# rgb-matrix-backpack-5a.net
KiCad netlist of a schematic drawn in EAGLE
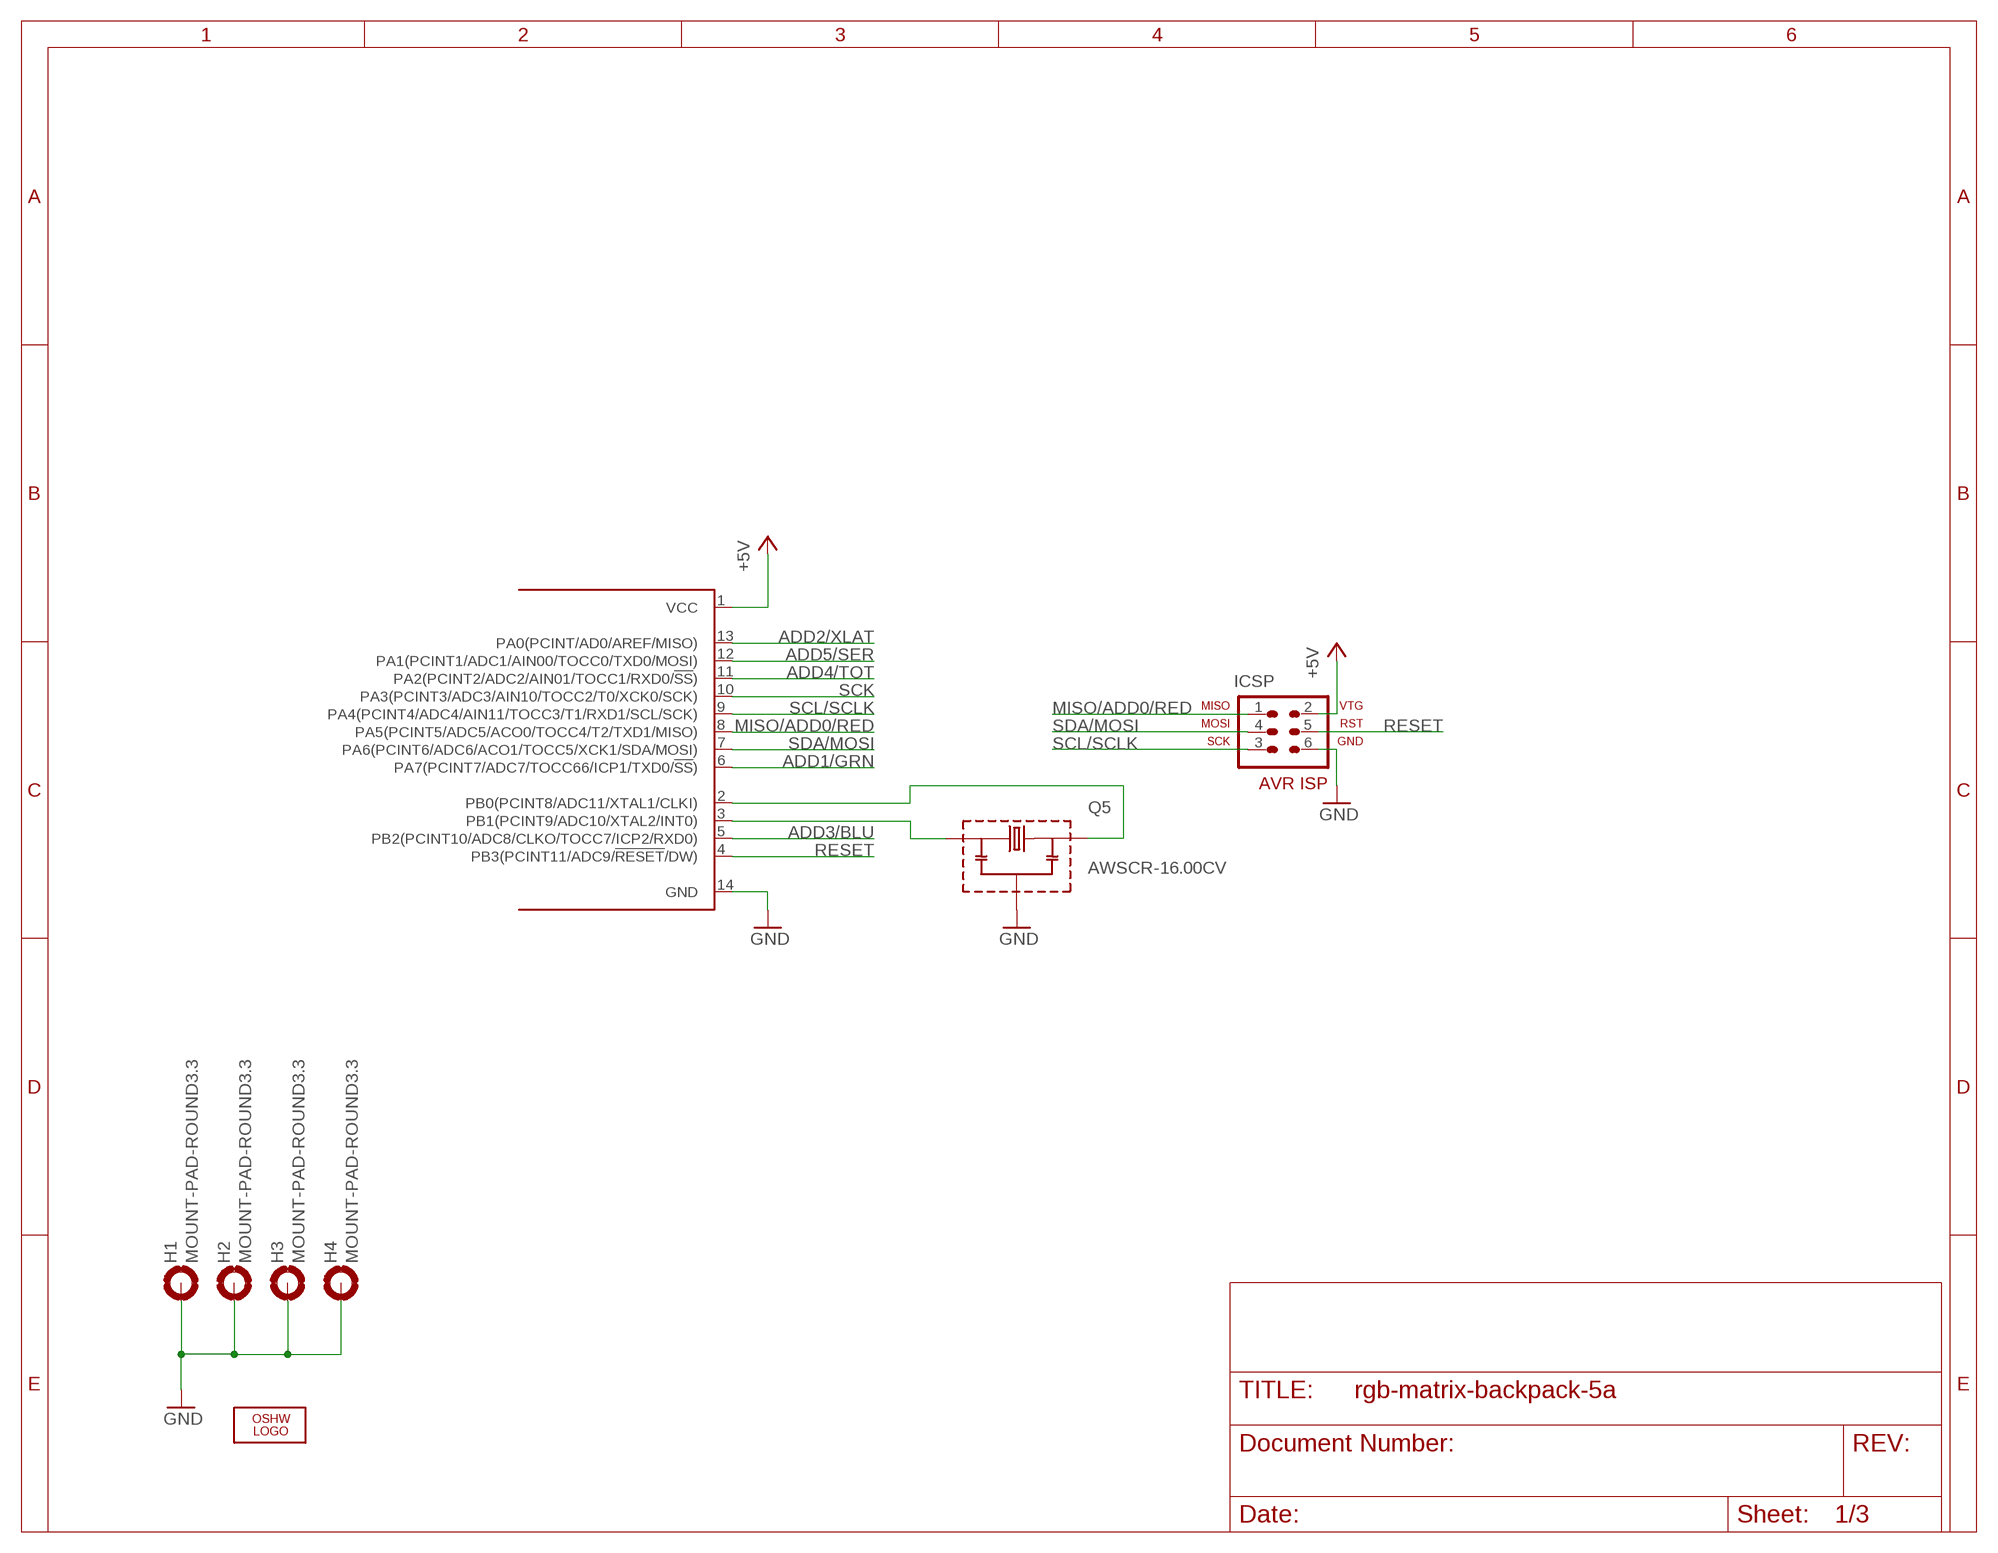
[diagram p0: schematic, sheet 1]
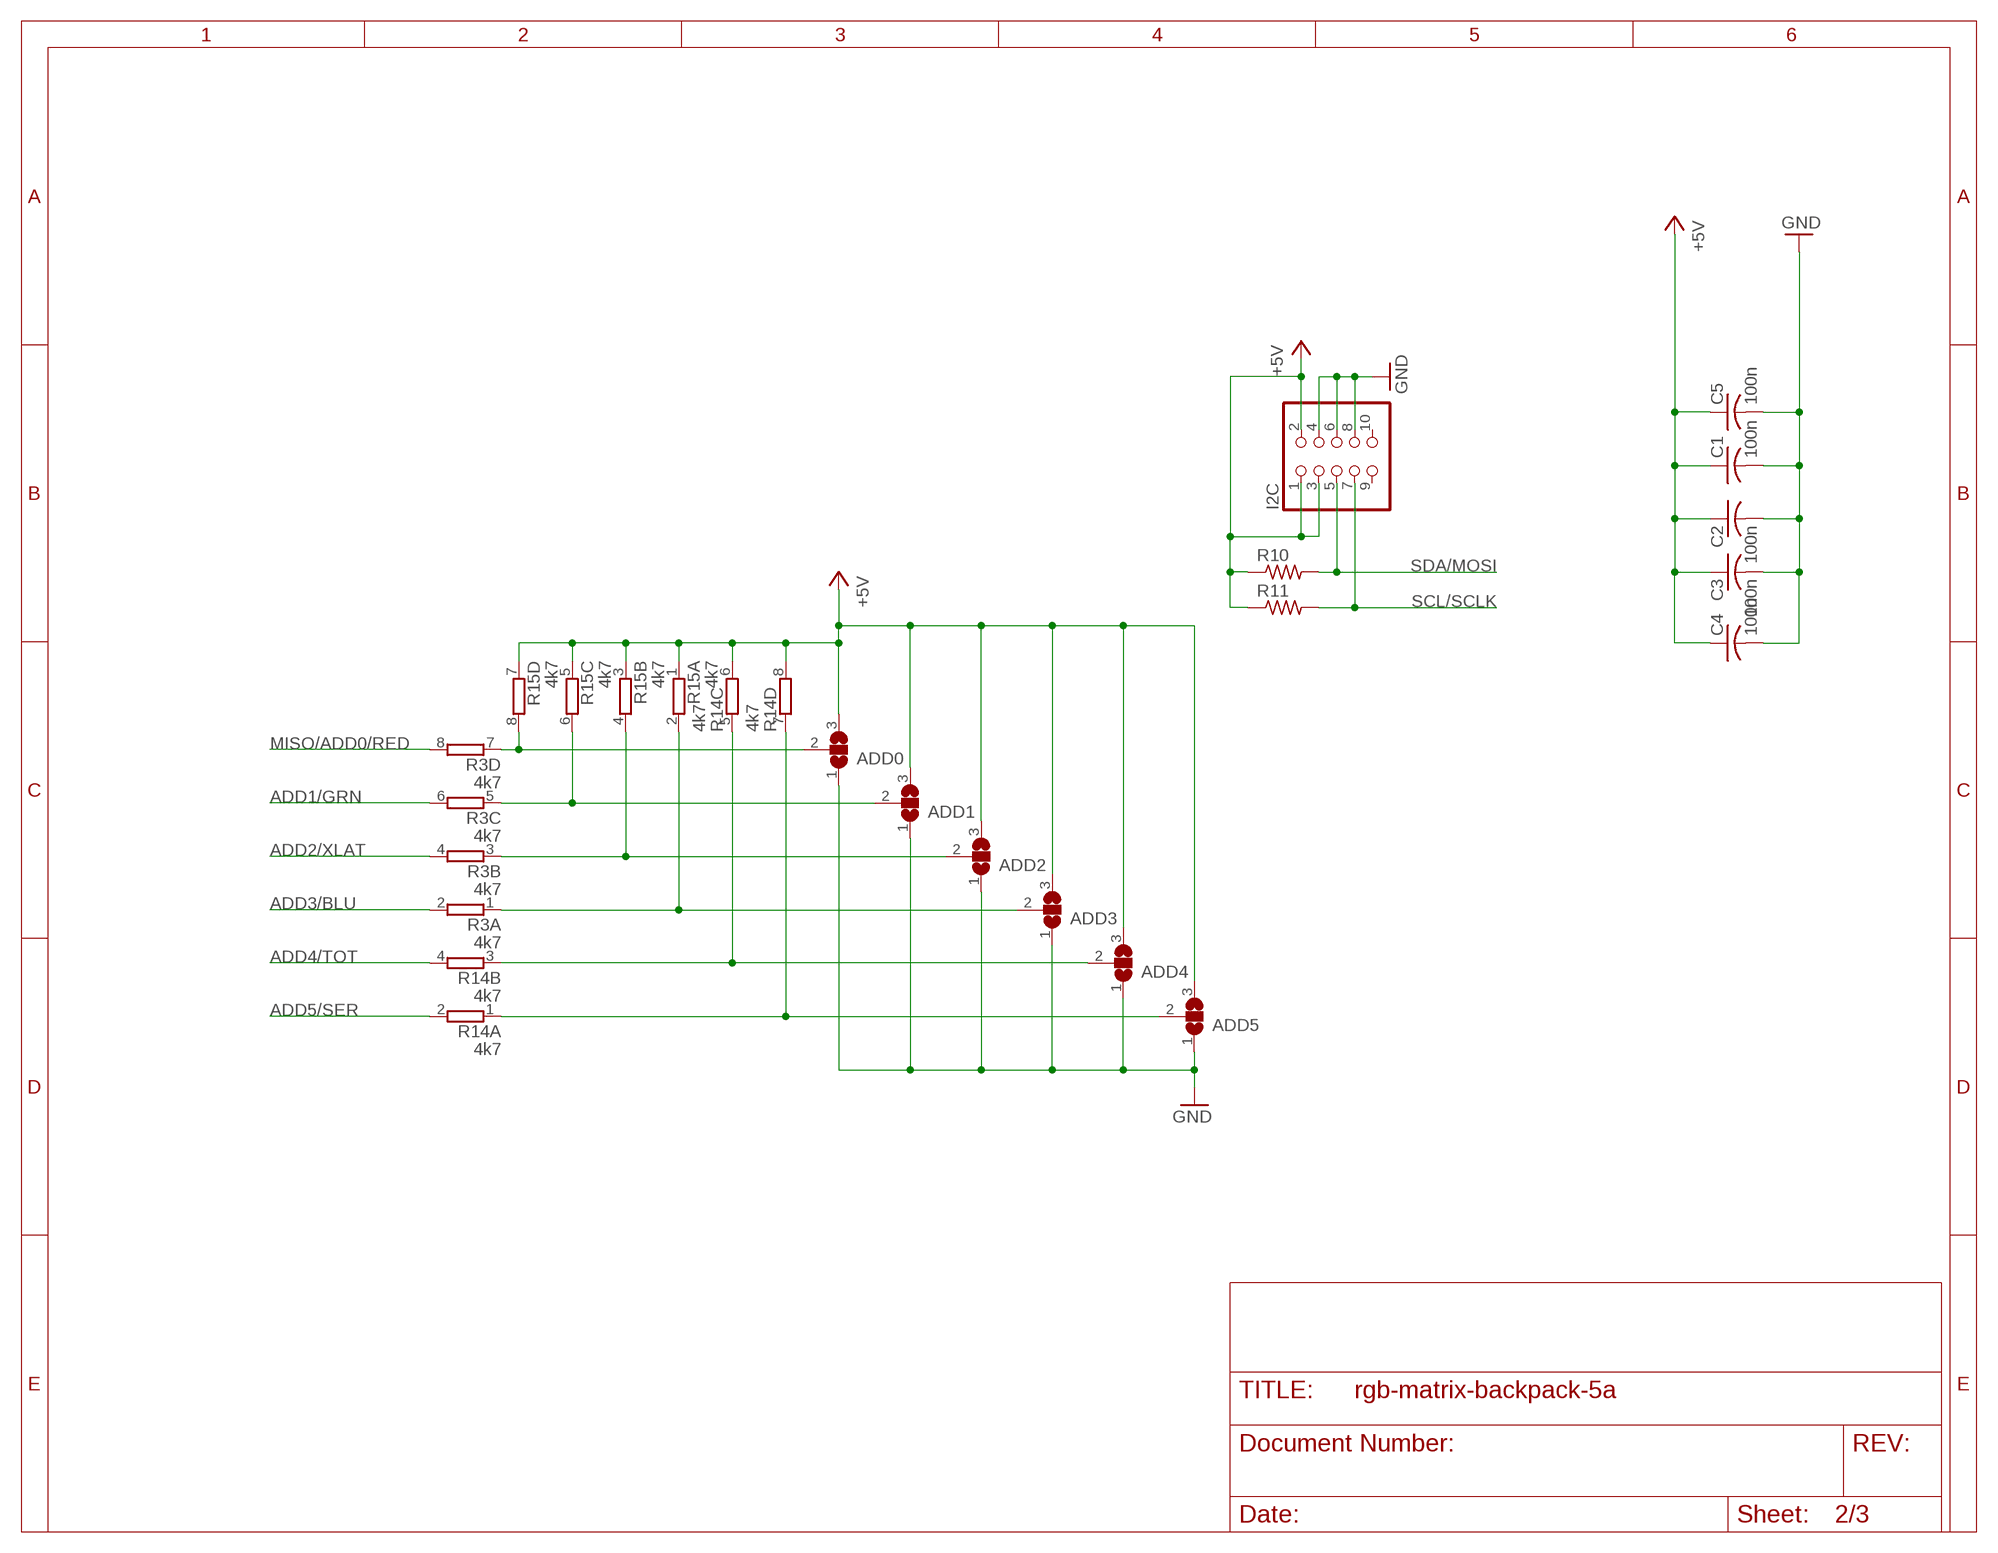
[diagram p1: schematic, sheet 2]
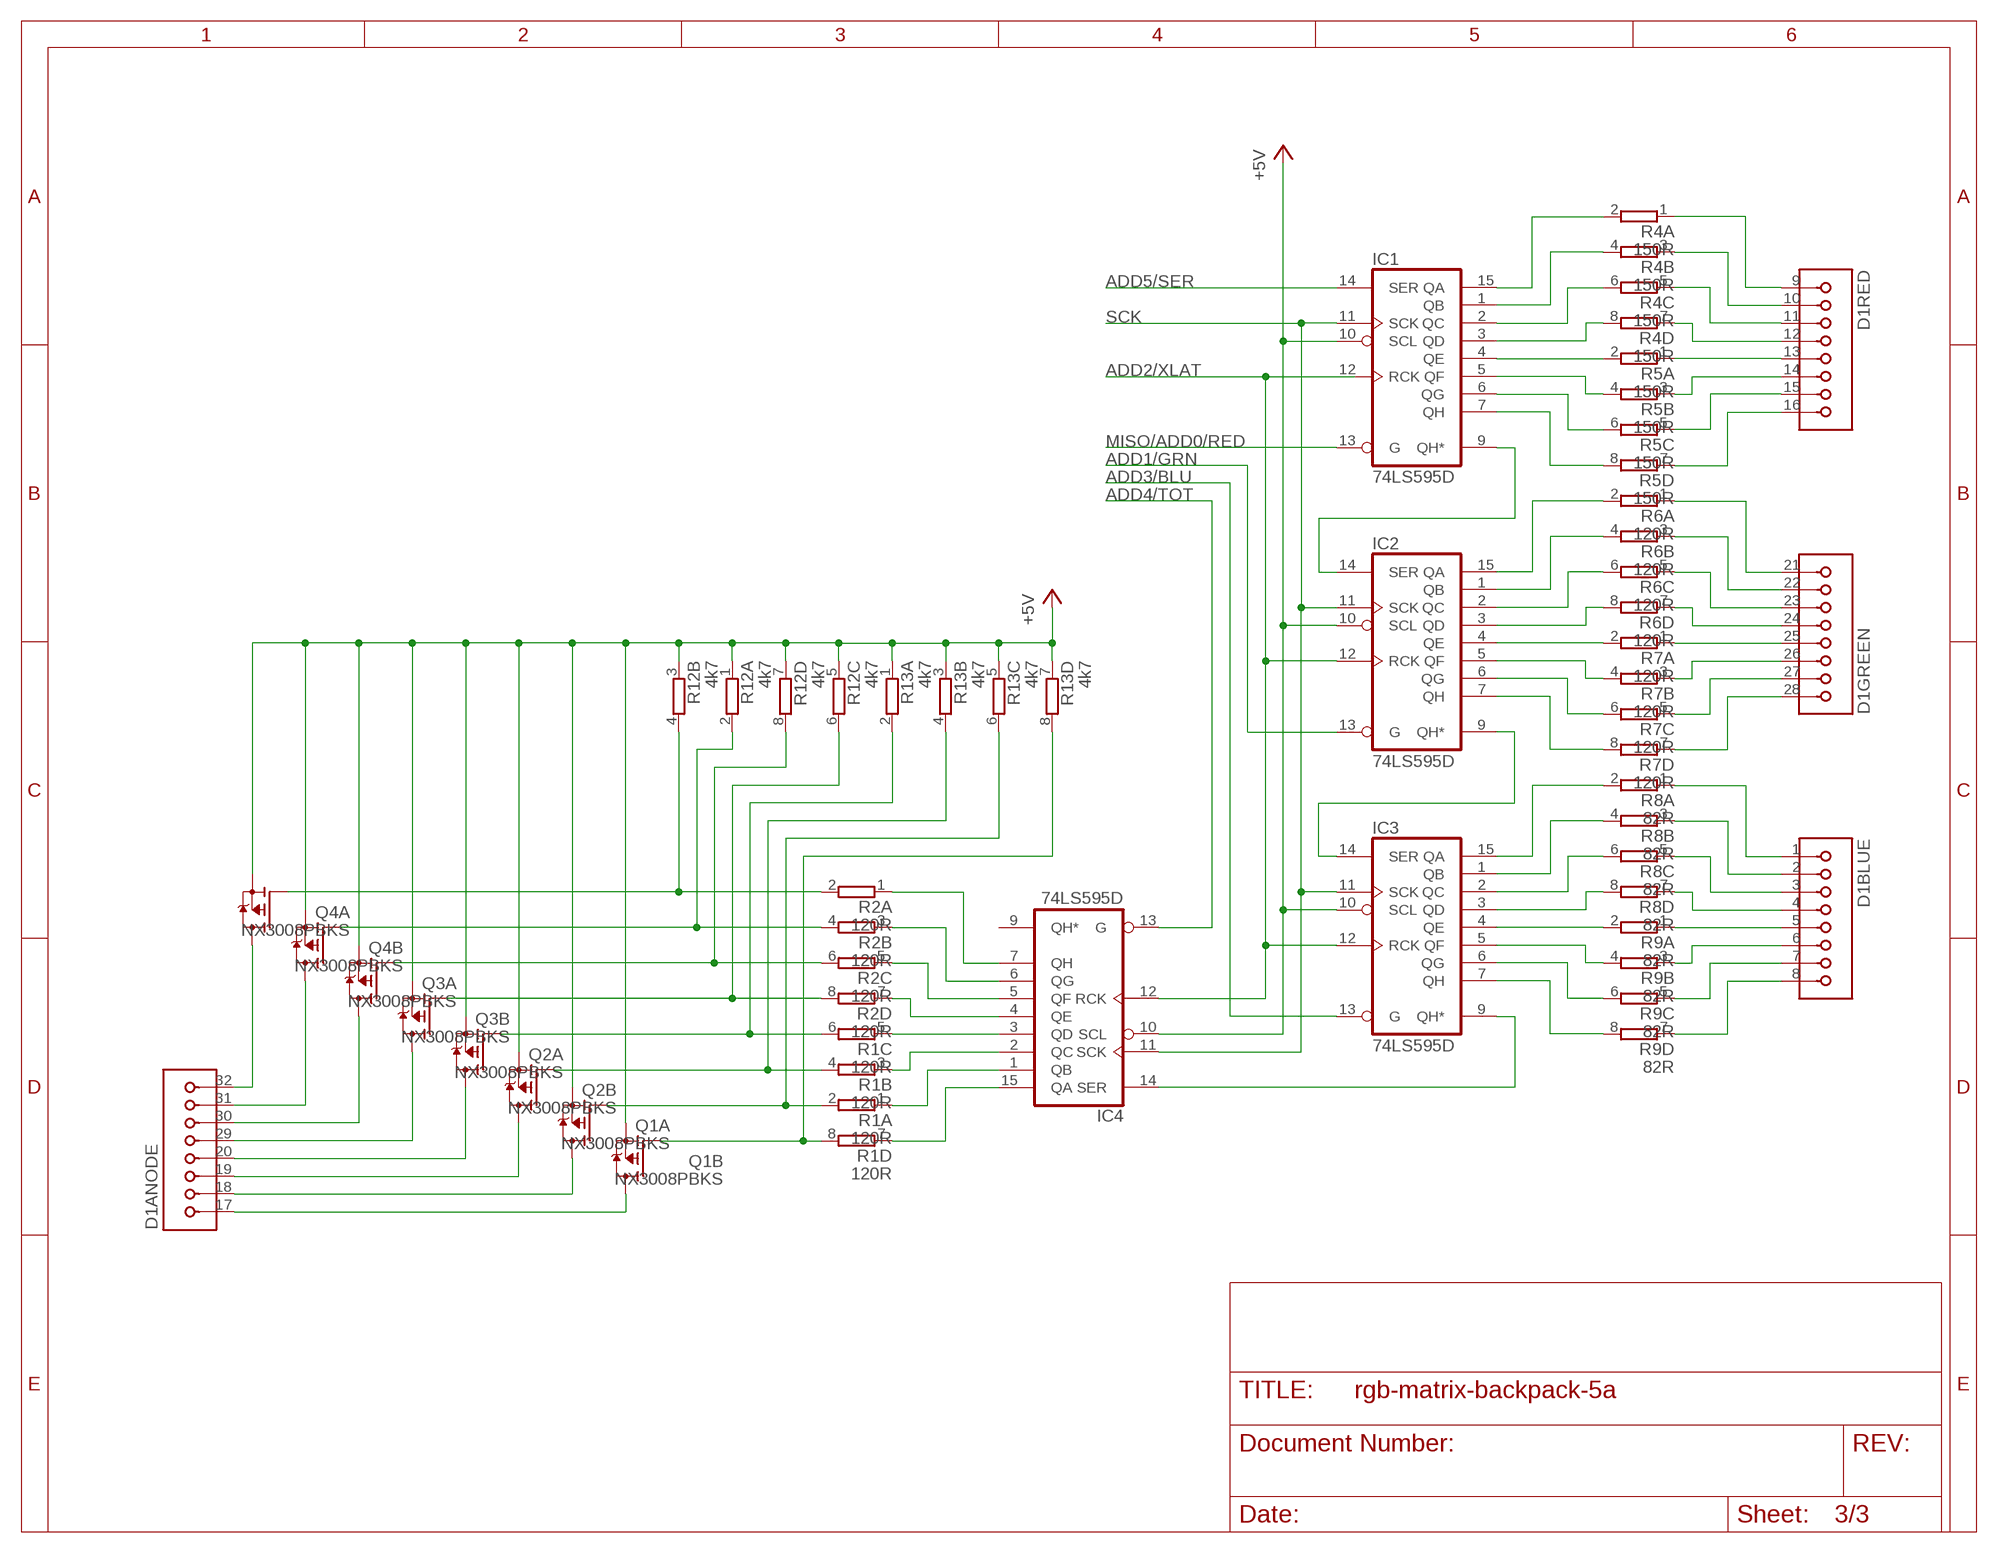
[diagram p2: schematic, sheet 3]

(export (version "E")
  (design (tool "Eeschema 10.0.6"))
  (components
    (comp (ref "ADD0")
      (value "SJ2W")
      (footprint "eagle-import:SJ_2")
      (libsource (lib "eagle-import") (part "SJ2W"))
    )
    (comp (ref "ADD1")
      (value "SJ2W")
      (footprint "eagle-import:SJ_2")
      (libsource (lib "eagle-import") (part "SJ2W"))
    )
    (comp (ref "ADD2")
      (value "SJ2W")
      (footprint "eagle-import:SJ_2")
      (libsource (lib "eagle-import") (part "SJ2W"))
    )
    (comp (ref "ADD3")
      (value "SJ2W")
      (footprint "eagle-import:SJ_2")
      (libsource (lib "eagle-import") (part "SJ2W"))
    )
    (comp (ref "ADD4")
      (value "SJ2W")
      (footprint "eagle-import:SJ_2")
      (libsource (lib "eagle-import") (part "SJ2W"))
    )
    (comp (ref "ADD5")
      (value "SJ2W")
      (footprint "eagle-import:SJ_2")
      (libsource (lib "eagle-import") (part "SJ2W"))
    )
    (comp (ref "C1")
      (value "100n")
      (footprint "eagle-import:C0603")
      (fields (field (name "PARTNO") "CC0603MRY5V9BB104"))
      (libsource (lib "eagle-import") (part "C-USC0603"))
    )
    (comp (ref "C2")
      (value "100n")
      (footprint "eagle-import:C0603")
      (fields (field (name "PARTNO") "CC0603MRY5V9BB104"))
      (libsource (lib "eagle-import") (part "C-USC0603"))
    )
    (comp (ref "C3")
      (value "100n")
      (footprint "eagle-import:C0603")
      (fields (field (name "PARTNO") "CC0603ZRY5V7BB105"))
      (libsource (lib "eagle-import") (part "C-USC0603"))
    )
    (comp (ref "C4")
      (value "100n")
      (footprint "eagle-import:C0603")
      (fields (field (name "PARTNO") "CC0603MRY5V9BB104"))
      (libsource (lib "eagle-import") (part "C-USC0603"))
    )
    (comp (ref "C5")
      (value "100n")
      (footprint "eagle-import:C0603")
      (fields (field (name "PARTNO") "CC0603MRY5V9BB104"))
      (libsource (lib "eagle-import") (part "C-USC0603"))
    )
    (comp (ref "I2C")
      (value "PINHD-2X5_2.54-90°")
      (footprint "eagle-import:2X05_90")
      (libsource (lib "eagle-import") (part "PINHD-2X5_2.54-90°"))
    )
    (comp (ref "R3")
      (value "4k7")
      (footprint "eagle-import:CTS742C083-RES")
      (fields (field (name "PARTNO") "742C083102JPTR"))
      (libsource (lib "eagle-import") (part "4R-NCTS742C083"))
    )
    (comp (ref "R10")
      (value "R-US_0207/2V")
      (footprint "eagle-import:0207_2V")
      (fields (field (name "PARTNO") "CF14JT4K70"))
      (libsource (lib "eagle-import") (part "R-US_0207/2V"))
    )
    (comp (ref "R11")
      (value "R-US_0207/2V")
      (footprint "eagle-import:0207_2V")
      (fields (field (name "PARTNO") "CF14JT4K70"))
      (libsource (lib "eagle-import") (part "R-US_0207/2V"))
    )
    (comp (ref "R14")
      (value "4k7")
      (footprint "eagle-import:CTS742C083-RES")
      (fields (field (name "PARTNO") "742C083102JPTR"))
      (libsource (lib "eagle-import") (part "4R-NCTS742C083"))
    )
    (comp (ref "R15")
      (value "4k7")
      (footprint "eagle-import:CTS742C083-RES")
      (fields (field (name "PARTNO") "742C083102JPTR"))
      (libsource (lib "eagle-import") (part "4R-NCTS742C083"))
    )
    (comp (ref "D1")
      (value "60MM-8X8-RGB-LED-ARRAY")
      (footprint "eagle-import:60MM-8X8-RGB-MATRIX")
      (fields (field (name "BOM") "EXCLUDE") (field (name "DNP") "T"))
      (libsource (lib "eagle-import") (part "60MM-8X8-RGB-LED-ARRAY"))
    )
    (comp (ref "IC1")
      (value "74LS595D")
      (footprint "eagle-import:SO16")
      (libsource (lib "eagle-import") (part "74595DLS"))
    )
    (comp (ref "IC2")
      (value "74LS595D")
      (footprint "eagle-import:SO16")
      (libsource (lib "eagle-import") (part "74595DLS"))
    )
    (comp (ref "IC3")
      (value "74LS595D")
      (footprint "eagle-import:SO16")
      (libsource (lib "eagle-import") (part "74595DLS"))
    )
    (comp (ref "IC4")
      (value "74LS595D")
      (footprint "eagle-import:SO16")
      (libsource (lib "eagle-import") (part "74595DLS"))
    )
    (comp (ref "Q1")
      (value "NX3008PBKS")
      (footprint "eagle-import:SOT363_INFINEON")
      (fields (field (name "PARTNO") "NX3008PBKS"))
      (libsource (lib "eagle-import") (part "BSD223P"))
    )
    (comp (ref "Q2")
      (value "NX3008PBKS")
      (footprint "eagle-import:SOT363_INFINEON")
      (libsource (lib "eagle-import") (part "BSD223P"))
    )
    (comp (ref "Q3")
      (value "NX3008PBKS")
      (footprint "eagle-import:SOT363_INFINEON")
      (libsource (lib "eagle-import") (part "BSD223P"))
    )
    (comp (ref "Q4")
      (value "NX3008PBKS")
      (footprint "eagle-import:SOT363_INFINEON")
      (libsource (lib "eagle-import") (part "BSD223P"))
    )
    (comp (ref "R1")
      (value "120R")
      (footprint "eagle-import:CTS742C083-RES")
      (fields (field (name "PARTNO") "742C083102JPTR"))
      (libsource (lib "eagle-import") (part "4R-NCTS742C083"))
    )
    (comp (ref "R2")
      (value "120R")
      (footprint "eagle-import:CTS742C083-RES")
      (fields (field (name "PARTNO") "742C083102JPTR"))
      (libsource (lib "eagle-import") (part "4R-NCTS742C083"))
    )
    (comp (ref "R4")
      (value "150R")
      (footprint "eagle-import:CTS742C083-RES")
      (fields (field (name "PARTNO") "742C083102JPTR"))
      (libsource (lib "eagle-import") (part "4R-NCTS742C083"))
    )
    (comp (ref "R5")
      (value "150R")
      (footprint "eagle-import:CTS742C083-RES")
      (fields (field (name "PARTNO") "742C083102JPTR"))
      (libsource (lib "eagle-import") (part "4R-NCTS742C083"))
    )
    (comp (ref "R6")
      (value "120R")
      (footprint "eagle-import:CTS742C083-RES")
      (fields (field (name "PARTNO") "742C083102JPTR"))
      (libsource (lib "eagle-import") (part "4R-NCTS742C083"))
    )
    (comp (ref "R7")
      (value "120R")
      (footprint "eagle-import:CTS742C083-RES")
      (fields (field (name "PARTNO") "742C083102JPTR"))
      (libsource (lib "eagle-import") (part "4R-NCTS742C083"))
    )
    (comp (ref "R8")
      (value "82R")
      (footprint "eagle-import:CTS742C083-RES")
      (fields (field (name "PARTNO") "742C083102JPTR"))
      (libsource (lib "eagle-import") (part "4R-NCTS742C083"))
    )
    (comp (ref "R9")
      (value "82R")
      (footprint "eagle-import:CTS742C083-RES")
      (fields (field (name "PARTNO") "742C083102JPTR"))
      (libsource (lib "eagle-import") (part "4R-NCTS742C083"))
    )
    (comp (ref "R12")
      (value "4k7")
      (footprint "eagle-import:CTS742C083-RES")
      (fields (field (name "PARTNO") "742C083102JPTR"))
      (libsource (lib "eagle-import") (part "4R-NCTS742C083"))
    )
    (comp (ref "R13")
      (value "4k7")
      (footprint "eagle-import:CTS742C083-RES")
      (fields (field (name "PARTNO") "742C083102JPTR"))
      (libsource (lib "eagle-import") (part "4R-NCTS742C083"))
    )
    (comp (ref "H1")
      (value "MOUNT-PAD-ROUND3.3")
      (footprint "eagle-import:3,3-PAD")
      (libsource (lib "eagle-import") (part "MOUNT-PAD-ROUND3.3"))
    )
    (comp (ref "H2")
      (value "MOUNT-PAD-ROUND3.3")
      (footprint "eagle-import:3,3-PAD")
      (libsource (lib "eagle-import") (part "MOUNT-PAD-ROUND3.3"))
    )
    (comp (ref "H3")
      (value "MOUNT-PAD-ROUND3.3")
      (footprint "eagle-import:3,3-PAD")
      (libsource (lib "eagle-import") (part "MOUNT-PAD-ROUND3.3"))
    )
    (comp (ref "H4")
      (value "MOUNT-PAD-ROUND3.3")
      (footprint "eagle-import:3,3-PAD")
      (libsource (lib "eagle-import") (part "MOUNT-PAD-ROUND3.3"))
    )
    (comp (ref "ICSP")
      (value "AVR-ISP-6")
      (footprint "eagle-import:AVR-ISP-6")
      (libsource (lib "eagle-import") (part "AVR-ISP-6"))
    )
    (comp (ref "LOGO1")
      (value "OSHW_LOGO_FILLX0350-NT")
      (footprint "eagle-import:OSHW_FILLX350_NOTEXT")
      (libsource (lib "eagle-import") (part "OSHW_LOGO_FILLX0350-NT"))
    )
    (comp (ref "Q5")
      (value "AWSCR-16.00CV")
      (footprint "eagle-import:AWSCR")
      (libsource (lib "eagle-import") (part "AWSCR-16.00CV"))
    )
    (comp (ref "U1")
      (value "ATTINY841-SU")
      (footprint "eagle-import:SO14")
      (libsource (lib "eagle-import") (part "ATTINY841-SU"))
    )
  )
  (nets
    (net (code "1") (name "+5V") (class "Default")
      (node (ref "ADD0") (pin "3") (pinfunction "3_3") (pintype "passive"))
      (node (ref "ADD1") (pin "3") (pinfunction "3_3") (pintype "passive"))
      (node (ref "ADD2") (pin "3") (pinfunction "3_3") (pintype "passive"))
      (node (ref "ADD3") (pin "3") (pinfunction "3_3") (pintype "passive"))
      (node (ref "ADD4") (pin "3") (pinfunction "3_3") (pintype "passive"))
      (node (ref "ADD5") (pin "3") (pinfunction "3_3") (pintype "passive"))
      (node (ref "C1") (pin "1") (pinfunction "1_1") (pintype "passive"))
      (node (ref "C2") (pin "1") (pinfunction "1_1") (pintype "passive"))
      (node (ref "C3") (pin "1") (pinfunction "1_1") (pintype "passive"))
      (node (ref "C4") (pin "1") (pinfunction "1_1") (pintype "passive"))
      (node (ref "C5") (pin "1") (pinfunction "1_1") (pintype "passive"))
      (node (ref "I2C") (pin "1") (pinfunction "1_1") (pintype "passive"))
      (node (ref "I2C") (pin "2") (pinfunction "2_2") (pintype "passive"))
      (node (ref "I2C") (pin "3") (pinfunction "3_3") (pintype "passive"))
      (node (ref "IC1") (pin "10") (pinfunction "SCL_10") (pintype "input"))
      (node (ref "IC2") (pin "10") (pinfunction "SCL_10") (pintype "input"))
      (node (ref "IC3") (pin "10") (pinfunction "SCL_10") (pintype "input"))
      (node (ref "IC4") (pin "10") (pinfunction "SCL_10") (pintype "input"))
      (node (ref "ICSP") (pin "2") (pinfunction "2_2") (pintype "passive"))
      (node (ref "Q1") (pin "1") (pinfunction "S_1") (pintype "passive"))
      (node (ref "Q1") (pin "4") (pinfunction "S_4") (pintype "passive"))
      (node (ref "Q2") (pin "1") (pinfunction "S_1") (pintype "passive"))
      (node (ref "Q2") (pin "4") (pinfunction "S_4") (pintype "passive"))
      (node (ref "Q3") (pin "1") (pinfunction "S_1") (pintype "passive"))
      (node (ref "Q3") (pin "4") (pinfunction "S_4") (pintype "passive"))
      (node (ref "Q4") (pin "1") (pinfunction "S_1") (pintype "passive"))
      (node (ref "Q4") (pin "4") (pinfunction "S_4") (pintype "passive"))
      (node (ref "R10") (pin "1") (pinfunction "1_1") (pintype "passive"))
      (node (ref "R11") (pin "1") (pinfunction "1_1") (pintype "passive"))
      (node (ref "R12") (pin "1") (pinfunction "1_1") (pintype "passive"))
      (node (ref "R12") (pin "3") (pinfunction "1_3") (pintype "passive"))
      (node (ref "R12") (pin "5") (pinfunction "1_5") (pintype "passive"))
      (node (ref "R12") (pin "7") (pinfunction "1_7") (pintype "passive"))
      (node (ref "R13") (pin "1") (pinfunction "1_1") (pintype "passive"))
      (node (ref "R13") (pin "3") (pinfunction "1_3") (pintype "passive"))
      (node (ref "R13") (pin "5") (pinfunction "1_5") (pintype "passive"))
      (node (ref "R13") (pin "7") (pinfunction "1_7") (pintype "passive"))
      (node (ref "R14") (pin "6") (pinfunction "2_6") (pintype "passive"))
      (node (ref "R14") (pin "8") (pinfunction "2_8") (pintype "passive"))
      (node (ref "R15") (pin "1") (pinfunction "1_1") (pintype "passive"))
      (node (ref "R15") (pin "3") (pinfunction "1_3") (pintype "passive"))
      (node (ref "R15") (pin "5") (pinfunction "1_5") (pintype "passive"))
      (node (ref "R15") (pin "7") (pinfunction "1_7") (pintype "passive"))
      (node (ref "U1") (pin "1") (pinfunction "VCC_1") (pintype "bidirectional"))
    )
    (net (code "2") (name "ADD1{slash}GRN") (class "Default")
      (node (ref "IC2") (pin "13") (pinfunction "G_13") (pintype "input"))
      (node (ref "R3") (pin "6") (pinfunction "2_6") (pintype "passive"))
      (node (ref "U1") (pin "6") (pinfunction "PA7(PCINT7/ADC7/TOCC66/ICP1/TXD0/~{SS})_6") (pintype "bidirectional"))
    )
    (net (code "3") (name "ADD2{slash}XLAT") (class "Default")
      (node (ref "IC1") (pin "12") (pinfunction "RCK_12") (pintype "input"))
      (node (ref "IC2") (pin "12") (pinfunction "RCK_12") (pintype "input"))
      (node (ref "IC3") (pin "12") (pinfunction "RCK_12") (pintype "input"))
      (node (ref "IC4") (pin "12") (pinfunction "RCK_12") (pintype "input"))
      (node (ref "R3") (pin "4") (pinfunction "2_4") (pintype "passive"))
      (node (ref "U1") (pin "13") (pinfunction "PA0(PCINT/AD0/AREF/MISO)_13") (pintype "bidirectional"))
    )
    (net (code "4") (name "ADD3{slash}BLU") (class "Default")
      (node (ref "IC3") (pin "13") (pinfunction "G_13") (pintype "input"))
      (node (ref "R3") (pin "2") (pinfunction "2_2") (pintype "passive"))
      (node (ref "U1") (pin "5") (pinfunction "PB2(PCINT10/ADC8/CLKO/TOCC7/ICP2/RXD0)_5") (pintype "bidirectional"))
    )
    (net (code "5") (name "ADD4{slash}TOT") (class "Default")
      (node (ref "IC4") (pin "13") (pinfunction "G_13") (pintype "input"))
      (node (ref "R14") (pin "4") (pinfunction "2_4") (pintype "passive"))
      (node (ref "U1") (pin "11") (pinfunction "PA2(PCINT2/ADC2/AIN01/TOCC1/RXD0/~{SS})_11") (pintype "bidirectional"))
    )
    (net (code "6") (name "ADD5{slash}SER") (class "Default")
      (node (ref "IC1") (pin "14") (pinfunction "SER_14") (pintype "input"))
      (node (ref "R14") (pin "2") (pinfunction "2_2") (pintype "passive"))
      (node (ref "U1") (pin "12") (pinfunction "PA1(PCINT1/ADC1/AIN00/TOCC0/TXD0/MOSI)_12") (pintype "bidirectional"))
    )
    (net (code "7") (name "GND") (class "Default")
      (node (ref "ADD0") (pin "1") (pinfunction "1_1") (pintype "passive"))
      (node (ref "ADD1") (pin "1") (pinfunction "1_1") (pintype "passive"))
      (node (ref "ADD2") (pin "1") (pinfunction "1_1") (pintype "passive"))
      (node (ref "ADD3") (pin "1") (pinfunction "1_1") (pintype "passive"))
      (node (ref "ADD4") (pin "1") (pinfunction "1_1") (pintype "passive"))
      (node (ref "ADD5") (pin "1") (pinfunction "1_1") (pintype "passive"))
      (node (ref "C1") (pin "2") (pinfunction "2_2") (pintype "passive"))
      (node (ref "C2") (pin "2") (pinfunction "2_2") (pintype "passive"))
      (node (ref "C3") (pin "2") (pinfunction "2_2") (pintype "passive"))
      (node (ref "C4") (pin "2") (pinfunction "2_2") (pintype "passive"))
      (node (ref "C5") (pin "2") (pinfunction "2_2") (pintype "passive"))
      (node (ref "H1") (pin "B3,3") (pinfunction "MOUNT_B3,3") (pintype "passive"))
      (node (ref "H2") (pin "B3,3") (pinfunction "MOUNT_B3,3") (pintype "passive"))
      (node (ref "H3") (pin "B3,3") (pinfunction "MOUNT_B3,3") (pintype "passive"))
      (node (ref "H4") (pin "B3,3") (pinfunction "MOUNT_B3,3") (pintype "passive"))
      (node (ref "I2C") (pin "4") (pinfunction "4_4") (pintype "passive"))
      (node (ref "I2C") (pin "6") (pinfunction "6_6") (pintype "passive"))
      (node (ref "I2C") (pin "8") (pinfunction "8_8") (pintype "passive"))
      (node (ref "ICSP") (pin "6") (pinfunction "6_6") (pintype "passive"))
      (node (ref "Q5") (pin "2") (pinfunction "2_2") (pintype "passive"))
      (node (ref "U1") (pin "14") (pinfunction "GND_14") (pintype "bidirectional"))
    )
    (net (code "8") (name "MISO{slash}ADD0{slash}RED") (class "Default")
      (node (ref "IC1") (pin "13") (pinfunction "G_13") (pintype "input"))
      (node (ref "ICSP") (pin "1") (pinfunction "1_1") (pintype "passive"))
      (node (ref "R3") (pin "8") (pinfunction "2_8") (pintype "passive"))
      (node (ref "U1") (pin "8") (pinfunction "PA5(PCINT5/ADC5/ACO0/TOCC4/T2/TXD1/MISO)_8") (pintype "bidirectional"))
    )
    (net (code "9") (name "Net-(ADD3-Pad2)") (class "Default")
      (node (ref "ADD3") (pin "2") (pinfunction "2_2") (pintype "passive"))
      (node (ref "R15") (pin "2") (pinfunction "2_2") (pintype "passive"))
      (node (ref "R3") (pin "1") (pinfunction "1_1") (pintype "passive"))
    )
    (net (code "10") (name "Net-(D1-Pad1)") (class "Default")
      (node (ref "D1") (pin "1") (pinfunction "1_1") (pintype "bidirectional"))
      (node (ref "R8") (pin "1") (pinfunction "1_1") (pintype "passive"))
    )
    (net (code "11") (name "Net-(D1-Pad5)") (class "Default")
      (node (ref "D1") (pin "5") (pinfunction "5_5") (pintype "bidirectional"))
      (node (ref "R9") (pin "1") (pinfunction "1_1") (pintype "passive"))
    )
    (net (code "12") (name "Net-(D1A-1)") (class "Default")
      (node (ref "D1") (pin "17") (pinfunction "1_17") (pintype "bidirectional"))
      (node (ref "Q1") (pin "3") (pinfunction "D_3") (pintype "passive"))
    )
    (net (code "13") (name "Net-(D1A-2)") (class "Default")
      (node (ref "D1") (pin "18") (pinfunction "2_18") (pintype "bidirectional"))
      (node (ref "Q1") (pin "6") (pinfunction "D_6") (pintype "passive"))
    )
    (net (code "14") (name "Net-(D1A-3)") (class "Default")
      (node (ref "D1") (pin "19") (pinfunction "3_19") (pintype "bidirectional"))
      (node (ref "Q2") (pin "3") (pinfunction "D_3") (pintype "passive"))
    )
    (net (code "15") (name "Net-(D1A-4)") (class "Default")
      (node (ref "D1") (pin "20") (pinfunction "4_20") (pintype "bidirectional"))
      (node (ref "Q2") (pin "6") (pinfunction "D_6") (pintype "passive"))
    )
    (net (code "16") (name "Net-(D1A-5)") (class "Default")
      (node (ref "D1") (pin "29") (pinfunction "5_29") (pintype "bidirectional"))
      (node (ref "Q3") (pin "3") (pinfunction "D_3") (pintype "passive"))
    )
    (net (code "17") (name "Net-(D1A-6)") (class "Default")
      (node (ref "D1") (pin "30") (pinfunction "6_30") (pintype "bidirectional"))
      (node (ref "Q3") (pin "6") (pinfunction "D_6") (pintype "passive"))
    )
    (net (code "18") (name "Net-(D1A-7)") (class "Default")
      (node (ref "D1") (pin "31") (pinfunction "7_31") (pintype "bidirectional"))
      (node (ref "Q4") (pin "3") (pinfunction "D_3") (pintype "passive"))
    )
    (net (code "19") (name "Net-(D1A-8)") (class "Default")
      (node (ref "D1") (pin "32") (pinfunction "8_32") (pintype "bidirectional"))
      (node (ref "Q4") (pin "6") (pinfunction "D_6") (pintype "passive"))
    )
    (net (code "20") (name "Net-(D1C-1)") (class "Default")
      (node (ref "D1") (pin "28") (pinfunction "1_28") (pintype "bidirectional"))
      (node (ref "R7") (pin "7") (pinfunction "1_7") (pintype "passive"))
    )
    (net (code "21") (name "Net-(D1C-2)") (class "Default")
      (node (ref "D1") (pin "27") (pinfunction "2_27") (pintype "bidirectional"))
      (node (ref "R7") (pin "5") (pinfunction "1_5") (pintype "passive"))
    )
    (net (code "22") (name "Net-(D1C-3)") (class "Default")
      (node (ref "D1") (pin "26") (pinfunction "3_26") (pintype "bidirectional"))
      (node (ref "R7") (pin "3") (pinfunction "1_3") (pintype "passive"))
    )
    (net (code "23") (name "Net-(D1C-4)") (class "Default")
      (node (ref "D1") (pin "25") (pinfunction "4_25") (pintype "bidirectional"))
      (node (ref "R7") (pin "1") (pinfunction "1_1") (pintype "passive"))
    )
    (net (code "24") (name "Net-(D1C-5)") (class "Default")
      (node (ref "D1") (pin "24") (pinfunction "5_24") (pintype "bidirectional"))
      (node (ref "R6") (pin "7") (pinfunction "1_7") (pintype "passive"))
    )
    (net (code "25") (name "Net-(D1C-6)") (class "Default")
      (node (ref "D1") (pin "23") (pinfunction "6_23") (pintype "bidirectional"))
      (node (ref "R6") (pin "5") (pinfunction "1_5") (pintype "passive"))
    )
    (net (code "26") (name "Net-(D1C-7)") (class "Default")
      (node (ref "D1") (pin "22") (pinfunction "7_22") (pintype "bidirectional"))
      (node (ref "R6") (pin "3") (pinfunction "1_3") (pintype "passive"))
    )
    (net (code "27") (name "Net-(D1C-8)") (class "Default")
      (node (ref "D1") (pin "21") (pinfunction "8_21") (pintype "bidirectional"))
      (node (ref "R6") (pin "1") (pinfunction "1_1") (pintype "passive"))
    )
    (net (code "28") (name "Net-(D1D-1)") (class "Default")
      (node (ref "D1") (pin "9") (pinfunction "1_9") (pintype "bidirectional"))
      (node (ref "R4") (pin "1") (pinfunction "1_1") (pintype "passive"))
    )
    (net (code "29") (name "Net-(D1D-2)") (class "Default")
      (node (ref "D1") (pin "10") (pinfunction "2_10") (pintype "bidirectional"))
      (node (ref "R4") (pin "3") (pinfunction "1_3") (pintype "passive"))
    )
    (net (code "30") (name "Net-(D1D-3)") (class "Default")
      (node (ref "D1") (pin "11") (pinfunction "3_11") (pintype "bidirectional"))
      (node (ref "R4") (pin "5") (pinfunction "1_5") (pintype "passive"))
    )
    (net (code "31") (name "Net-(D1D-4)") (class "Default")
      (node (ref "D1") (pin "12") (pinfunction "4_12") (pintype "bidirectional"))
      (node (ref "R4") (pin "7") (pinfunction "1_7") (pintype "passive"))
    )
    (net (code "32") (name "Net-(D1D-5)") (class "Default")
      (node (ref "D1") (pin "13") (pinfunction "5_13") (pintype "bidirectional"))
      (node (ref "R5") (pin "1") (pinfunction "1_1") (pintype "passive"))
    )
    (net (code "33") (name "Net-(D1D-6)") (class "Default")
      (node (ref "D1") (pin "14") (pinfunction "6_14") (pintype "bidirectional"))
      (node (ref "R5") (pin "3") (pinfunction "1_3") (pintype "passive"))
    )
    (net (code "34") (name "Net-(D1D-7)") (class "Default")
      (node (ref "D1") (pin "15") (pinfunction "7_15") (pintype "bidirectional"))
      (node (ref "R5") (pin "5") (pinfunction "1_5") (pintype "passive"))
    )
    (net (code "35") (name "Net-(D1D-8)") (class "Default")
      (node (ref "D1") (pin "16") (pinfunction "8_16") (pintype "bidirectional"))
      (node (ref "R5") (pin "7") (pinfunction "1_7") (pintype "passive"))
    )
    (net (code "36") (name "Net-(IC1A-QA)") (class "Default")
      (node (ref "IC1") (pin "15") (pinfunction "QA_15") (pintype "tri_state"))
      (node (ref "R4") (pin "2") (pinfunction "2_2") (pintype "passive"))
    )
    (net (code "37") (name "Net-(IC1A-QB)") (class "Default")
      (node (ref "IC1") (pin "1") (pinfunction "QB_1") (pintype "tri_state"))
      (node (ref "R4") (pin "4") (pinfunction "2_4") (pintype "passive"))
    )
    (net (code "38") (name "Net-(IC1A-QC)") (class "Default")
      (node (ref "IC1") (pin "2") (pinfunction "QC_2") (pintype "tri_state"))
      (node (ref "R4") (pin "6") (pinfunction "2_6") (pintype "passive"))
    )
    (net (code "39") (name "Net-(IC1A-QD)") (class "Default")
      (node (ref "IC1") (pin "3") (pinfunction "QD_3") (pintype "tri_state"))
      (node (ref "R4") (pin "8") (pinfunction "2_8") (pintype "passive"))
    )
    (net (code "40") (name "Net-(IC1A-QE)") (class "Default")
      (node (ref "IC1") (pin "4") (pinfunction "QE_4") (pintype "tri_state"))
      (node (ref "R5") (pin "2") (pinfunction "2_2") (pintype "passive"))
    )
    (net (code "41") (name "Net-(IC1A-QF)") (class "Default")
      (node (ref "IC1") (pin "5") (pinfunction "QF_5") (pintype "tri_state"))
      (node (ref "R5") (pin "4") (pinfunction "2_4") (pintype "passive"))
    )
    (net (code "42") (name "Net-(IC1A-QG)") (class "Default")
      (node (ref "IC1") (pin "6") (pinfunction "QG_6") (pintype "tri_state"))
      (node (ref "R5") (pin "6") (pinfunction "2_6") (pintype "passive"))
    )
    (net (code "43") (name "Net-(IC1A-QH)") (class "Default")
      (node (ref "IC1") (pin "7") (pinfunction "QH_7") (pintype "tri_state"))
      (node (ref "R5") (pin "8") (pinfunction "2_8") (pintype "passive"))
    )
    (net (code "44") (name "Net-(IC1A-QH*)") (class "Default")
      (node (ref "IC1") (pin "9") (pinfunction "QH*_9") (pintype "tri_state"))
      (node (ref "IC2") (pin "14") (pinfunction "SER_14") (pintype "input"))
    )
    (net (code "45") (name "Net-(IC2A-QA)") (class "Default")
      (node (ref "IC2") (pin "15") (pinfunction "QA_15") (pintype "tri_state"))
      (node (ref "R6") (pin "2") (pinfunction "2_2") (pintype "passive"))
    )
    (net (code "46") (name "Net-(IC2A-QB)") (class "Default")
      (node (ref "IC2") (pin "1") (pinfunction "QB_1") (pintype "tri_state"))
      (node (ref "R6") (pin "4") (pinfunction "2_4") (pintype "passive"))
    )
    (net (code "47") (name "Net-(IC2A-QC)") (class "Default")
      (node (ref "IC2") (pin "2") (pinfunction "QC_2") (pintype "tri_state"))
      (node (ref "R6") (pin "6") (pinfunction "2_6") (pintype "passive"))
    )
    (net (code "48") (name "Net-(IC2A-QD)") (class "Default")
      (node (ref "IC2") (pin "3") (pinfunction "QD_3") (pintype "tri_state"))
      (node (ref "R6") (pin "8") (pinfunction "2_8") (pintype "passive"))
    )
    (net (code "49") (name "Net-(IC2A-QE)") (class "Default")
      (node (ref "IC2") (pin "4") (pinfunction "QE_4") (pintype "tri_state"))
      (node (ref "R7") (pin "2") (pinfunction "2_2") (pintype "passive"))
    )
    (net (code "50") (name "Net-(IC2A-QF)") (class "Default")
      (node (ref "IC2") (pin "5") (pinfunction "QF_5") (pintype "tri_state"))
      (node (ref "R7") (pin "4") (pinfunction "2_4") (pintype "passive"))
    )
    (net (code "51") (name "Net-(IC2A-QG)") (class "Default")
      (node (ref "IC2") (pin "6") (pinfunction "QG_6") (pintype "tri_state"))
      (node (ref "R7") (pin "6") (pinfunction "2_6") (pintype "passive"))
    )
    (net (code "52") (name "Net-(IC2A-QH)") (class "Default")
      (node (ref "IC2") (pin "7") (pinfunction "QH_7") (pintype "tri_state"))
      (node (ref "R7") (pin "8") (pinfunction "2_8") (pintype "passive"))
    )
    (net (code "53") (name "Net-(IC2A-QH*)") (class "Default")
      (node (ref "IC2") (pin "9") (pinfunction "QH*_9") (pintype "tri_state"))
      (node (ref "IC3") (pin "14") (pinfunction "SER_14") (pintype "input"))
    )
    (net (code "54") (name "Net-(IC3A-QA)") (class "Default")
      (node (ref "IC3") (pin "15") (pinfunction "QA_15") (pintype "tri_state"))
      (node (ref "R8") (pin "2") (pinfunction "2_2") (pintype "passive"))
    )
    (net (code "55") (name "Net-(IC3A-QB)") (class "Default")
      (node (ref "IC3") (pin "1") (pinfunction "QB_1") (pintype "tri_state"))
      (node (ref "R8") (pin "4") (pinfunction "2_4") (pintype "passive"))
    )
    (net (code "56") (name "Net-(IC3A-QC)") (class "Default")
      (node (ref "IC3") (pin "2") (pinfunction "QC_2") (pintype "tri_state"))
      (node (ref "R8") (pin "6") (pinfunction "2_6") (pintype "passive"))
    )
    (net (code "57") (name "Net-(IC3A-QD)") (class "Default")
      (node (ref "IC3") (pin "3") (pinfunction "QD_3") (pintype "tri_state"))
      (node (ref "R8") (pin "8") (pinfunction "2_8") (pintype "passive"))
    )
    (net (code "58") (name "Net-(IC3A-QE)") (class "Default")
      (node (ref "IC3") (pin "4") (pinfunction "QE_4") (pintype "tri_state"))
      (node (ref "R9") (pin "2") (pinfunction "2_2") (pintype "passive"))
    )
    (net (code "59") (name "Net-(IC3A-QF)") (class "Default")
      (node (ref "IC3") (pin "5") (pinfunction "QF_5") (pintype "tri_state"))
      (node (ref "R9") (pin "4") (pinfunction "2_4") (pintype "passive"))
    )
    (net (code "60") (name "Net-(IC3A-QG)") (class "Default")
      (node (ref "IC3") (pin "6") (pinfunction "QG_6") (pintype "tri_state"))
      (node (ref "R9") (pin "6") (pinfunction "2_6") (pintype "passive"))
    )
    (net (code "61") (name "Net-(IC3A-QH)") (class "Default")
      (node (ref "IC3") (pin "7") (pinfunction "QH_7") (pintype "tri_state"))
      (node (ref "R9") (pin "8") (pinfunction "2_8") (pintype "passive"))
    )
    (net (code "62") (name "Net-(IC3A-QH*)") (class "Default")
      (node (ref "IC3") (pin "9") (pinfunction "QH*_9") (pintype "tri_state"))
      (node (ref "IC4") (pin "14") (pinfunction "SER_14") (pintype "input"))
    )
    (net (code "63") (name "Net-(IC4A-QA)") (class "Default")
      (node (ref "IC4") (pin "15") (pinfunction "QA_15") (pintype "tri_state"))
      (node (ref "R1") (pin "7") (pinfunction "1_7") (pintype "passive"))
    )
    (net (code "64") (name "Net-(IC4A-QB)") (class "Default")
      (node (ref "IC4") (pin "1") (pinfunction "QB_1") (pintype "tri_state"))
      (node (ref "R1") (pin "1") (pinfunction "1_1") (pintype "passive"))
    )
    (net (code "65") (name "Net-(IC4A-QC)") (class "Default")
      (node (ref "IC4") (pin "2") (pinfunction "QC_2") (pintype "tri_state"))
      (node (ref "R1") (pin "3") (pinfunction "1_3") (pintype "passive"))
    )
    (net (code "66") (name "Net-(IC4A-QD)") (class "Default")
      (node (ref "IC4") (pin "3") (pinfunction "QD_3") (pintype "tri_state"))
      (node (ref "R1") (pin "5") (pinfunction "1_5") (pintype "passive"))
    )
    (net (code "67") (name "Net-(IC4A-QE)") (class "Default")
      (node (ref "IC4") (pin "4") (pinfunction "QE_4") (pintype "tri_state"))
      (node (ref "R2") (pin "7") (pinfunction "1_7") (pintype "passive"))
    )
    (net (code "68") (name "Net-(IC4A-QF)") (class "Default")
      (node (ref "IC4") (pin "5") (pinfunction "QF_5") (pintype "tri_state"))
      (node (ref "R2") (pin "5") (pinfunction "1_5") (pintype "passive"))
    )
    (net (code "69") (name "Net-(IC4A-QG)") (class "Default")
      (node (ref "IC4") (pin "6") (pinfunction "QG_6") (pintype "tri_state"))
      (node (ref "R2") (pin "3") (pinfunction "1_3") (pintype "passive"))
    )
    (net (code "70") (name "Net-(IC4A-QH)") (class "Default")
      (node (ref "IC4") (pin "7") (pinfunction "QH_7") (pintype "tri_state"))
      (node (ref "R2") (pin "1") (pinfunction "1_1") (pintype "passive"))
    )
    (net (code "71") (name "Net-(Q1A-G)") (class "Default")
      (node (ref "Q1") (pin "2") (pinfunction "G_2") (pintype "passive"))
      (node (ref "R1") (pin "2") (pinfunction "2_2") (pintype "passive"))
      (node (ref "R13") (pin "6") (pinfunction "2_6") (pintype "passive"))
    )
    (net (code "72") (name "Net-(Q1B-G)") (class "Default")
      (node (ref "Q1") (pin "5") (pinfunction "G_5") (pintype "passive"))
      (node (ref "R1") (pin "8") (pinfunction "2_8") (pintype "passive"))
      (node (ref "R13") (pin "8") (pinfunction "2_8") (pintype "passive"))
    )
    (net (code "73") (name "Net-(Q2A-G)") (class "Default")
      (node (ref "Q2") (pin "2") (pinfunction "G_2") (pintype "passive"))
      (node (ref "R1") (pin "6") (pinfunction "2_6") (pintype "passive"))
      (node (ref "R13") (pin "2") (pinfunction "2_2") (pintype "passive"))
    )
    (net (code "74") (name "Net-(Q2B-G)") (class "Default")
      (node (ref "Q2") (pin "5") (pinfunction "G_5") (pintype "passive"))
      (node (ref "R1") (pin "4") (pinfunction "2_4") (pintype "passive"))
      (node (ref "R13") (pin "4") (pinfunction "2_4") (pintype "passive"))
    )
    (net (code "75") (name "Net-(Q3A-G)") (class "Default")
      (node (ref "Q3") (pin "2") (pinfunction "G_2") (pintype "passive"))
      (node (ref "R12") (pin "8") (pinfunction "2_8") (pintype "passive"))
      (node (ref "R2") (pin "6") (pinfunction "2_6") (pintype "passive"))
    )
    (net (code "76") (name "Net-(Q3B-G)") (class "Default")
      (node (ref "Q3") (pin "5") (pinfunction "G_5") (pintype "passive"))
      (node (ref "R12") (pin "6") (pinfunction "2_6") (pintype "passive"))
      (node (ref "R2") (pin "8") (pinfunction "2_8") (pintype "passive"))
    )
    (net (code "77") (name "Net-(Q4A-G)") (class "Default")
      (node (ref "Q4") (pin "2") (pinfunction "G_2") (pintype "passive"))
      (node (ref "R12") (pin "4") (pinfunction "2_4") (pintype "passive"))
      (node (ref "R2") (pin "2") (pinfunction "2_2") (pintype "passive"))
    )
    (net (code "78") (name "Net-(Q4B-G)") (class "Default")
      (node (ref "Q4") (pin "5") (pinfunction "G_5") (pintype "passive"))
      (node (ref "R12") (pin "2") (pinfunction "2_2") (pintype "passive"))
      (node (ref "R2") (pin "4") (pinfunction "2_4") (pintype "passive"))
    )
    (net (code "79") (name "Net-(R8B-1)") (class "Default")
      (node (ref "D1") (pin "2") (pinfunction "2_2") (pintype "bidirectional"))
      (node (ref "R8") (pin "3") (pinfunction "1_3") (pintype "passive"))
    )
    (net (code "80") (name "Net-(R8C-1)") (class "Default")
      (node (ref "D1") (pin "3") (pinfunction "3_3") (pintype "bidirectional"))
      (node (ref "R8") (pin "5") (pinfunction "1_5") (pintype "passive"))
    )
    (net (code "81") (name "Net-(R8D-1)") (class "Default")
      (node (ref "D1") (pin "4") (pinfunction "4_4") (pintype "bidirectional"))
      (node (ref "R8") (pin "7") (pinfunction "1_7") (pintype "passive"))
    )
    (net (code "82") (name "Net-(R9B-1)") (class "Default")
      (node (ref "D1") (pin "6") (pinfunction "6_6") (pintype "bidirectional"))
      (node (ref "R9") (pin "3") (pinfunction "1_3") (pintype "passive"))
    )
    (net (code "83") (name "Net-(R9C-1)") (class "Default")
      (node (ref "D1") (pin "7") (pinfunction "7_7") (pintype "bidirectional"))
      (node (ref "R9") (pin "5") (pinfunction "1_5") (pintype "passive"))
    )
    (net (code "84") (name "Net-(R9D-1)") (class "Default")
      (node (ref "D1") (pin "8") (pinfunction "8_8") (pintype "bidirectional"))
      (node (ref "R9") (pin "7") (pinfunction "1_7") (pintype "passive"))
    )
    (net (code "85") (name "Net-(R14B-1)") (class "Default")
      (node (ref "ADD4") (pin "2") (pinfunction "2_2") (pintype "passive"))
      (node (ref "R14") (pin "3") (pinfunction "1_3") (pintype "passive"))
      (node (ref "R14") (pin "5") (pinfunction "1_5") (pintype "passive"))
    )
    (net (code "86") (name "Net-(R14D-1)") (class "Default")
      (node (ref "ADD5") (pin "2") (pinfunction "2_2") (pintype "passive"))
      (node (ref "R14") (pin "1") (pinfunction "1_1") (pintype "passive"))
      (node (ref "R14") (pin "7") (pinfunction "1_7") (pintype "passive"))
    )
    (net (code "87") (name "Net-(R15B-2)") (class "Default")
      (node (ref "ADD2") (pin "2") (pinfunction "2_2") (pintype "passive"))
      (node (ref "R15") (pin "4") (pinfunction "2_4") (pintype "passive"))
      (node (ref "R3") (pin "3") (pinfunction "1_3") (pintype "passive"))
    )
    (net (code "88") (name "Net-(R15C-2)") (class "Default")
      (node (ref "ADD1") (pin "2") (pinfunction "2_2") (pintype "passive"))
      (node (ref "R15") (pin "6") (pinfunction "2_6") (pintype "passive"))
      (node (ref "R3") (pin "5") (pinfunction "1_5") (pintype "passive"))
    )
    (net (code "89") (name "Net-(R15D-2)") (class "Default")
      (node (ref "ADD0") (pin "2") (pinfunction "2_2") (pintype "passive"))
      (node (ref "R15") (pin "8") (pinfunction "2_8") (pintype "passive"))
      (node (ref "R3") (pin "7") (pinfunction "1_7") (pintype "passive"))
    )
    (net (code "90") (name "Net-(U1-PB0(PCINT8{slash}ADC11{slash}XTAL1{slash}CLKI))") (class "Default")
      (node (ref "Q5") (pin "3") (pinfunction "3_3") (pintype "passive"))
      (node (ref "U1") (pin "2") (pinfunction "PB0(PCINT8/ADC11/XTAL1/CLKI)_2") (pintype "bidirectional"))
    )
    (net (code "91") (name "Net-(U1-PB1(PCINT9{slash}ADC10{slash}XTAL2{slash}INT0))") (class "Default")
      (node (ref "Q5") (pin "1") (pinfunction "1_1") (pintype "passive"))
      (node (ref "U1") (pin "3") (pinfunction "PB1(PCINT9/ADC10/XTAL2/INT0)_3") (pintype "bidirectional"))
    )
    (net (code "92") (name "RESET") (class "Default")
      (node (ref "ICSP") (pin "5") (pinfunction "5_5") (pintype "passive"))
      (node (ref "U1") (pin "4") (pinfunction "PB3(PCINT11/ADC9/~{RESET}/DW)_4") (pintype "bidirectional"))
    )
    (net (code "93") (name "SCK") (class "Default")
      (node (ref "IC1") (pin "11") (pinfunction "SCK_11") (pintype "input"))
      (node (ref "IC2") (pin "11") (pinfunction "SCK_11") (pintype "input"))
      (node (ref "IC3") (pin "11") (pinfunction "SCK_11") (pintype "input"))
      (node (ref "IC4") (pin "11") (pinfunction "SCK_11") (pintype "input"))
      (node (ref "U1") (pin "10") (pinfunction "PA3(PCINT3/ADC3/AIN10/TOCC2/T0/XCK0/SCK)_10") (pintype "bidirectional"))
    )
    (net (code "94") (name "SCL{slash}SCLK") (class "Default")
      (node (ref "I2C") (pin "7") (pinfunction "7_7") (pintype "passive"))
      (node (ref "ICSP") (pin "3") (pinfunction "3_3") (pintype "passive"))
      (node (ref "R11") (pin "2") (pinfunction "2_2") (pintype "passive"))
      (node (ref "U1") (pin "9") (pinfunction "PA4(PCINT4/ADC4/AIN11/TOCC3/T1/RXD1/SCL/SCK)_9") (pintype "bidirectional"))
    )
    (net (code "95") (name "SDA{slash}MOSI") (class "Default")
      (node (ref "I2C") (pin "5") (pinfunction "5_5") (pintype "passive"))
      (node (ref "ICSP") (pin "4") (pinfunction "4_4") (pintype "passive"))
      (node (ref "R10") (pin "2") (pinfunction "2_2") (pintype "passive"))
      (node (ref "U1") (pin "7") (pinfunction "PA6(PCINT6/ADC6/ACO1/TOCC5/XCK1/SDA/MOSI)_7") (pintype "bidirectional"))
    )
    (net (code "96") (name "unconnected-(I2C-Pad9)") (class "Default")
      (node (ref "I2C") (pin "9") (pinfunction "9_9") (pintype "passive"))
    )
    (net (code "97") (name "unconnected-(I2C-Pad10)") (class "Default")
      (node (ref "I2C") (pin "10") (pinfunction "10_10") (pintype "passive"))
    )
    (net (code "98") (name "unconnected-(IC4A-QH*-Pad9)") (class "Default")
      (node (ref "IC4") (pin "9") (pinfunction "QH*_9") (pintype "tri_state"))
    )
  )
)
